# USB.net
KiCad netlist of a schematic drawn in Altium Designer
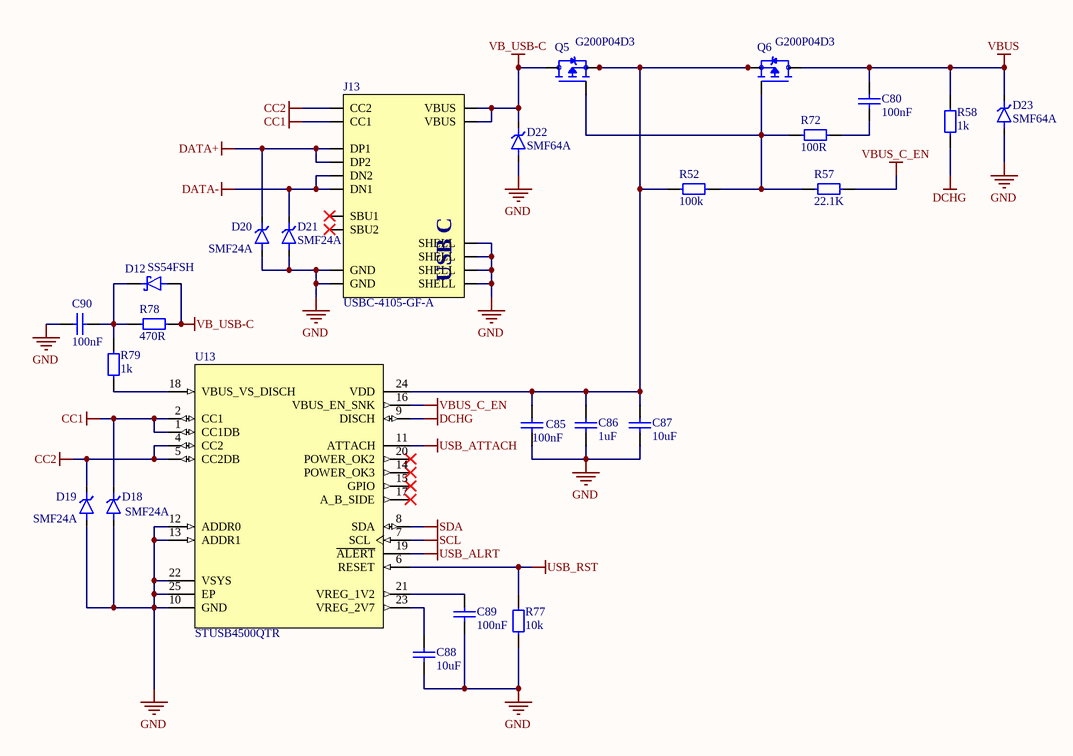
[diagram p0: USB.SchDoc]

(export (version "E")
  (design (tool "Eeschema 10.0.6"))
  (components
    (comp (ref "C80")
      (value "100nF")
      (footprint "0603 Capacitor")
      (description "100nF 50V 0603")
      (fields (field (name "MP") "KGF15AR71H104KM"))
      (libsource (lib "Capacitor") (part "Capacitor 100nF 0603"))
    )
    (comp (ref "C85")
      (value "100nF")
      (footprint "0603 Capacitor")
      (description "100nF 50V 0603")
      (fields (field (name "MP") "KGF15AR71H104KM"))
      (libsource (lib "Capacitor") (part "Capacitor 100nF 0603"))
    )
    (comp (ref "C86")
      (value "1uF")
      (footprint "0603 Capacitor")
      (description "1uF 50V 0603")
      (libsource (lib "Capacitor") (part "Capacitor 1uF 0603"))
    )
    (comp (ref "C87")
      (value "10uF")
      (footprint "0603 Capacitor")
      (description "10uF 10V 0603")
      (libsource (lib "Capacitor") (part "Capacitor 10uF 0603"))
    )
    (comp (ref "C88")
      (value "10uF")
      (footprint "0603 Capacitor")
      (description "10uF 10V 0603")
      (libsource (lib "Capacitor") (part "Capacitor 10uF 0603"))
    )
    (comp (ref "C89")
      (value "100nF")
      (footprint "0603 Capacitor")
      (description "100nF 50V 0603")
      (fields (field (name "MP") "KGF15AR71H104KM"))
      (libsource (lib "Capacitor") (part "Capacitor 100nF 0603"))
    )
    (comp (ref "C90")
      (value "100nF")
      (footprint "0603 Capacitor")
      (description "100nF 50V 0603")
      (fields (field (name "MP") "KGF15AR71H104KM"))
      (libsource (lib "Capacitor") (part "Capacitor 100nF 0603"))
    )
    (comp (ref "D12")
      (value "SS54FSH")
      (footprint "SODFL4725X110N")
      (description "5A, 40V, Schottky Rectifier")
      (fields (field (name "MF") "Taiwan Semiconductor"))
      (libsource (lib "Diode") (part "SS54FSH"))
    )
    (comp (ref "D18")
      (value "SMF24A")
      (footprint "SOD3718X102N")
      (description "1-channel  24V ultra-low-capacitance IEC ESD protection diode")
      (fields (field (name "MF") "Texas Instruments") (field (name "MP") "TPD1E05U06DPYR"))
      (libsource (lib "TVS") (part "SMF24A"))
    )
    (comp (ref "D19")
      (value "SMF24A")
      (footprint "SOD3718X102N")
      (description "1-channel  24V ultra-low-capacitance IEC ESD protection diode")
      (fields (field (name "MF") "Texas Instruments") (field (name "MP") "TPD1E05U06DPYR"))
      (libsource (lib "TVS") (part "SMF24A"))
    )
    (comp (ref "D20")
      (value "SMF24A")
      (footprint "SOD3718X102N")
      (description "1-channel  24V ultra-low-capacitance IEC ESD protection diode")
      (fields (field (name "MF") "Texas Instruments") (field (name "MP") "TPD1E05U06DPYR"))
      (libsource (lib "TVS") (part "SMF24A"))
    )
    (comp (ref "D21")
      (value "SMF24A")
      (footprint "SOD3718X102N")
      (description "1-channel  24V ultra-low-capacitance IEC ESD protection diode")
      (fields (field (name "MF") "Texas Instruments") (field (name "MP") "TPD1E05U06DPYR"))
      (libsource (lib "TVS") (part "SMF24A"))
    )
    (comp (ref "D22")
      (value "SMF64A")
      (footprint "SOD3718X102N")
      (description "1-channel  64V ultra-low-capacitance IEC ESD protection diode")
      (fields (field (name "MF") "Texas Instruments") (field (name "MP") "TPD1E05U06DPYR"))
      (libsource (lib "TVS") (part "SMF64A"))
    )
    (comp (ref "D23")
      (value "SMF64A")
      (footprint "SOD3718X102N")
      (description "1-channel  64V ultra-low-capacitance IEC ESD protection diode")
      (fields (field (name "MF") "Texas Instruments") (field (name "MP") "TPD1E05U06DPYR"))
      (libsource (lib "TVS") (part "SMF64A"))
    )
    (comp (ref "J13")
      (value "USBC-4105-GF-A")
      (footprint "GCT_USB4105-GF-A")
      (fields (field (name "MF") "{'manufacturer': u'GCT'}"))
      (libsource (lib "Connector") (part "USBC-4105-GF-A"))
    )
    (comp (ref "Q5")
      (value "G200P04D3")
      (footprint "TRANS_AONR21321")
      (description "P-Channel 40 V 20A Surface")
      (fields (field (name "MF") "onsemi") (field (name "MP") "BSS138"))
      (libsource (lib "Transistor") (part "G200P04D3"))
    )
    (comp (ref "Q6")
      (value "G200P04D3")
      (footprint "TRANS_AONR21321")
      (description "P-Channel 40 V 20A Surface")
      (fields (field (name "MF") "onsemi") (field (name "MP") "BSS138"))
      (libsource (lib "Transistor") (part "G200P04D3"))
    )
    (comp (ref "R52")
      (value "100k")
      (footprint "0603 Resistor")
      (description "100k 0603")
      (fields (field (name "MP") "RCG0603100KFKEA"))
      (libsource (lib "Resistors") (part "Resistor 100k 0603"))
    )
    (comp (ref "R57")
      (value "22.1K")
      (footprint "0603 Resistor")
      (description "22.1K 0603")
      (libsource (lib "Resistors") (part "Resistor 22.1K 0603"))
    )
    (comp (ref "R58")
      (value "1k")
      (footprint "0603 Resistor")
      (description "1k 0603")
      (libsource (lib "Resistors") (part "Resistor 1k 0603"))
    )
    (comp (ref "R72")
      (value "100R")
      (footprint "0603 Resistor")
      (description "100R 0603")
      (fields (field (name "MANUFACTURER_PART_NUMBER") "RE0603FRE07100RL"))
      (libsource (lib "Resistors") (part "Resistor 100R 0603"))
    )
    (comp (ref "R77")
      (value "10k")
      (footprint "0603 Resistor")
      (description "10k 0603")
      (fields (field (name "MP") "RE0603FRE1310KL"))
      (libsource (lib "Resistors") (part "Resistor 10k 0603"))
    )
    (comp (ref "R78")
      (value "470R")
      (footprint "0603 Resistor")
      (description "470R 0603")
      (libsource (lib "Resistors") (part "Resistor 470R 0603"))
    )
    (comp (ref "R79")
      (value "1k")
      (footprint "0603 Resistor")
      (description "1k 0603")
      (libsource (lib "Resistors") (part "Resistor 1k 0603"))
    )
    (comp (ref "U13")
      (value "STUSB4500QTR")
      (footprint "QFN50P400X400X90-25N")
      (description "USB Controller USB 2.0 I2C Interface 24-QFN (4x4)")
      (fields (field (name "MF") "STMicroelectronics"))
      (libsource (lib "IC") (part "STUSB4500QTR"))
    )
  )
  (nets
    (net (code "1") (name "CC1") (class "Default")
      (node (ref "D18") (pin "C") (pinfunction "K1_C") (pintype "passive"))
      (node (ref "J13") (pin "A5") (pinfunction "CC1_A5") (pintype "bidirectional"))
      (node (ref "U13") (pin "1") (pinfunction "CC1DB_1") (pintype "bidirectional"))
      (node (ref "U13") (pin "2") (pinfunction "CC1_2") (pintype "bidirectional"))
    )
    (net (code "2") (name "CC2") (class "Default")
      (node (ref "D19") (pin "C") (pinfunction "K1_C") (pintype "passive"))
      (node (ref "J13") (pin "B5") (pinfunction "CC2_B5") (pintype "bidirectional"))
      (node (ref "U13") (pin "4") (pinfunction "CC2_4") (pintype "bidirectional"))
      (node (ref "U13") (pin "5") (pinfunction "CC2DB_5") (pintype "bidirectional"))
    )
    (net (code "3") (name "DATA+") (class "Default")
      (node (ref "D20") (pin "C") (pinfunction "K1_C") (pintype "passive"))
      (node (ref "J13") (pin "A6") (pinfunction "DP1_A6") (pintype "bidirectional"))
      (node (ref "J13") (pin "B6") (pinfunction "DP2_B6") (pintype "bidirectional"))
    )
    (net (code "4") (name "DATA-") (class "Default")
      (node (ref "D21") (pin "C") (pinfunction "K1_C") (pintype "passive"))
      (node (ref "J13") (pin "A7") (pinfunction "DN1_A7") (pintype "bidirectional"))
      (node (ref "J13") (pin "B7") (pinfunction "DN2_B7") (pintype "bidirectional"))
    )
    (net (code "5") (name "DCHG") (class "Default")
      (node (ref "R58") (pin "1") (pinfunction "CCW_1") (pintype "passive"))
      (node (ref "U13") (pin "9") (pinfunction "DISCH_9") (pintype "bidirectional"))
    )
    (net (code "6") (name "GND") (class "Default")
      (node (ref "C85") (pin "1") (pinfunction "1_1") (pintype "passive"))
      (node (ref "C86") (pin "1") (pinfunction "1_1") (pintype "passive"))
      (node (ref "C87") (pin "1") (pinfunction "1_1") (pintype "passive"))
      (node (ref "C88") (pin "1") (pinfunction "1_1") (pintype "passive"))
      (node (ref "C89") (pin "1") (pinfunction "1_1") (pintype "passive"))
      (node (ref "C90") (pin "1") (pinfunction "1_1") (pintype "passive"))
      (node (ref "D18") (pin "A") (pinfunction "2_A") (pintype "passive"))
      (node (ref "D19") (pin "A") (pinfunction "2_A") (pintype "passive"))
      (node (ref "D20") (pin "A") (pinfunction "2_A") (pintype "passive"))
      (node (ref "D21") (pin "A") (pinfunction "2_A") (pintype "passive"))
      (node (ref "D22") (pin "A") (pinfunction "2_A") (pintype "passive"))
      (node (ref "D23") (pin "A") (pinfunction "2_A") (pintype "passive"))
      (node (ref "J13") (pin "A1_B12") (pinfunction "GND_A1_B12") (pintype "power_in"))
      (node (ref "J13") (pin "B1_A12") (pinfunction "GND_B1_A12") (pintype "power_in"))
      (node (ref "J13") (pin "SH1") (pinfunction "SHELL_SH1") (pintype "power_in"))
      (node (ref "J13") (pin "SH2") (pinfunction "SHELL_SH2") (pintype "power_in"))
      (node (ref "J13") (pin "SH3") (pinfunction "SHELL_SH3") (pintype "power_in"))
      (node (ref "J13") (pin "SH4") (pinfunction "SHELL_SH4") (pintype "power_in"))
      (node (ref "R77") (pin "1") (pinfunction "CCW_1") (pintype "passive"))
      (node (ref "U13") (pin "10") (pinfunction "GND_10") (pintype "power_in"))
      (node (ref "U13") (pin "12") (pinfunction "ADDR0_12") (pintype "input"))
      (node (ref "U13") (pin "13") (pinfunction "ADDR1_13") (pintype "input"))
      (node (ref "U13") (pin "22") (pinfunction "VSYS_22") (pintype "power_in"))
      (node (ref "U13") (pin "25") (pinfunction "EP_25") (pintype "power_in"))
    )
    (net (code "7") (name "Net-(D12-K)") (class "Default")
      (node (ref "C90") (pin "2") (pinfunction "2_2") (pintype "passive"))
      (node (ref "D12") (pin "C") (pinfunction "K_C") (pintype "passive"))
      (node (ref "R78") (pin "1") (pinfunction "CCW_1") (pintype "passive"))
      (node (ref "R79") (pin "1") (pinfunction "CCW_1") (pintype "passive"))
    )
    (net (code "8") (name "Net-(Q5-G)") (class "Default")
      (node (ref "Q5") (pin "4") (pinfunction "G_4") (pintype "passive"))
      (node (ref "Q6") (pin "4") (pinfunction "G_4") (pintype "passive"))
      (node (ref "R52") (pin "2") (pinfunction "CW_2") (pintype "passive"))
      (node (ref "R57") (pin "1") (pinfunction "CCW_1") (pintype "passive"))
      (node (ref "R72") (pin "1") (pinfunction "CCW_1") (pintype "passive"))
    )
    (net (code "9") (name "Net-(R52-CCW)") (class "Default")
      (node (ref "C85") (pin "2") (pinfunction "2_2") (pintype "passive"))
      (node (ref "C86") (pin "2") (pinfunction "2_2") (pintype "passive"))
      (node (ref "C87") (pin "2") (pinfunction "2_2") (pintype "passive"))
      (node (ref "Q5") (pin "1") (pinfunction "S_1") (pintype "passive"))
      (node (ref "Q5") (pin "2") (pinfunction "S_2") (pintype "passive"))
      (node (ref "Q5") (pin "3") (pinfunction "S_3") (pintype "passive"))
      (node (ref "Q6") (pin "1") (pinfunction "S_1") (pintype "passive"))
      (node (ref "Q6") (pin "2") (pinfunction "S_2") (pintype "passive"))
      (node (ref "Q6") (pin "3") (pinfunction "S_3") (pintype "passive"))
      (node (ref "R52") (pin "1") (pinfunction "CCW_1") (pintype "passive"))
      (node (ref "U13") (pin "24") (pinfunction "VDD_24") (pintype "power_in"))
    )
    (net (code "10") (name "Net-(R72-CW)") (class "Default")
      (node (ref "C80") (pin "1") (pinfunction "1_1") (pintype "passive"))
      (node (ref "R72") (pin "2") (pinfunction "CW_2") (pintype "passive"))
    )
    (net (code "11") (name "Net-(R79-CW)") (class "Default")
      (node (ref "R79") (pin "2") (pinfunction "CW_2") (pintype "passive"))
      (node (ref "U13") (pin "18") (pinfunction "VBUS_VS_DISCH_18") (pintype "input"))
    )
    (net (code "12") (name "Net-(U13-VREG_1V2)") (class "Default")
      (node (ref "C89") (pin "2") (pinfunction "2_2") (pintype "passive"))
      (node (ref "U13") (pin "21") (pinfunction "VREG_1V2_21") (pintype "output"))
    )
    (net (code "13") (name "Net-(U13-VREG_2V7)") (class "Default")
      (node (ref "C88") (pin "2") (pinfunction "2_2") (pintype "passive"))
      (node (ref "U13") (pin "23") (pinfunction "VREG_2V7_23") (pintype "output"))
    )
    (net (code "14") (name "SCL") (class "Default")
      (node (ref "U13") (pin "7") (pinfunction "SCL_7") (pintype "input"))
    )
    (net (code "15") (name "SDA") (class "Default")
      (node (ref "U13") (pin "8") (pinfunction "SDA_8") (pintype "bidirectional"))
    )
    (net (code "16") (name "USB_ALRT") (class "Default")
      (node (ref "U13") (pin "19") (pinfunction "~{ALERT}_19") (pintype "passive"))
    )
    (net (code "17") (name "USB_ATTACH") (class "Default")
      (node (ref "U13") (pin "11") (pinfunction "ATTACH_11") (pintype "passive"))
    )
    (net (code "18") (name "USB_RST") (class "Default")
      (node (ref "R77") (pin "2") (pinfunction "CW_2") (pintype "passive"))
      (node (ref "U13") (pin "6") (pinfunction "RESET_6") (pintype "input"))
    )
    (net (code "19") (name "VBUS") (class "Default")
      (node (ref "C80") (pin "2") (pinfunction "2_2") (pintype "passive"))
      (node (ref "D23") (pin "C") (pinfunction "K1_C") (pintype "passive"))
      (node (ref "Q6") (pin "5") (pinfunction "D_5") (pintype "passive"))
      (node (ref "R58") (pin "2") (pinfunction "CW_2") (pintype "passive"))
    )
    (net (code "20") (name "VBUS_C_EN") (class "Default")
      (node (ref "R57") (pin "2") (pinfunction "CW_2") (pintype "passive"))
      (node (ref "U13") (pin "16") (pinfunction "VBUS_EN_SNK_16") (pintype "output"))
    )
    (net (code "21") (name "VB_USB-C") (class "Default")
      (node (ref "D12") (pin "A") (pinfunction "A_A") (pintype "passive"))
      (node (ref "D22") (pin "C") (pinfunction "K1_C") (pintype "passive"))
      (node (ref "J13") (pin "A4_B9") (pinfunction "VBUS_A4_B9") (pintype "power_in"))
      (node (ref "J13") (pin "B4_A9") (pinfunction "VBUS_B4_A9") (pintype "power_in"))
      (node (ref "Q5") (pin "5") (pinfunction "D_5") (pintype "passive"))
      (node (ref "R78") (pin "2") (pinfunction "CW_2") (pintype "passive"))
    )
    (net (code "22") (name "unconnected-(J13-SBU1-PadA8)") (class "Default")
      (node (ref "J13") (pin "A8") (pinfunction "SBU1_A8") (pintype "bidirectional+no_connect"))
    )
    (net (code "23") (name "unconnected-(J13-SBU2-PadB8)") (class "Default")
      (node (ref "J13") (pin "B8") (pinfunction "SBU2_B8") (pintype "bidirectional+no_connect"))
    )
    (net (code "24") (name "unconnected-(U13-A_B_SIDE-Pad17)") (class "Default")
      (node (ref "U13") (pin "17") (pinfunction "A_B_SIDE_17") (pintype "output+no_connect"))
    )
    (net (code "25") (name "unconnected-(U13-GPIO-Pad15)") (class "Default")
      (node (ref "U13") (pin "15") (pinfunction "GPIO_15") (pintype "output+no_connect"))
    )
    (net (code "26") (name "unconnected-(U13-POWER_OK2-Pad20)") (class "Default")
      (node (ref "U13") (pin "20") (pinfunction "POWER_OK2_20") (pintype "output+no_connect"))
    )
    (net (code "27") (name "unconnected-(U13-POWER_OK3-Pad14)") (class "Default")
      (node (ref "U13") (pin "14") (pinfunction "POWER_OK3_14") (pintype "output+no_connect"))
    )
  )
)
